# CATS-EUROC-USB.net
KiCad netlist of a schematic drawn in Altium Designer
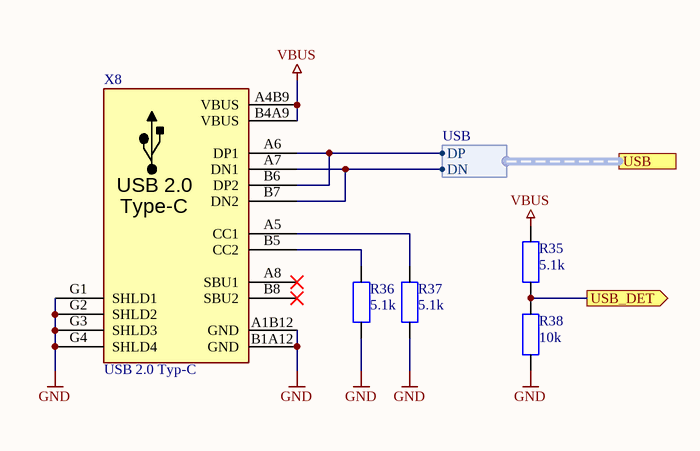
[diagram p0: CATS-EUROC-USB.SchDoc]

(export (version "E")
  (design (tool "Eeschema 10.0.6"))
  (components
    (comp (ref "R35")
      (value "5.1k")
      (footprint "SMD Widerstand 0402")
      (description "SMD Chip Resistor E24")
      (libsource (lib "CATS-EUROC") (part "E24 - 5.1k"))
    )
    (comp (ref "R36")
      (value "5.1k")
      (footprint "SMD Widerstand 0402")
      (description "SMD Chip Resistor E24")
      (libsource (lib "") (part "E24 - 5.1k_1"))
    )
    (comp (ref "R37")
      (value "5.1k")
      (footprint "SMD Widerstand 0402")
      (description "SMD Chip Resistor E24")
      (libsource (lib "") (part "E24 - 5.1k_1"))
    )
    (comp (ref "R38")
      (value "10k")
      (footprint "SMD Widerstand 0402")
      (description "SMD Chip Resistor E24")
      (libsource (lib "CATS-EUROC") (part "E24 - 10k"))
    )
    (comp (ref "X8")
      (value "USB 2.0 Typ-C")
      (footprint "THT USB-C Socket (A40-00119)")
      (description "Typ-C")
      (libsource (lib "CATS-EUROC") (part "USB Type-C USB 2.0"))
    )
  )
  (nets
    (net (code "2") (name "/USB_DET") (class "Default")
      (node (ref "R35") (pin "2") (pinfunction "2_2") (pintype "passive"))
      (node (ref "R38") (pin "1") (pinfunction "1_1") (pintype "passive"))
    )
    (net (code "4") (name "GND") (class "Default")
      (node (ref "R36") (pin "1") (pinfunction "1_1") (pintype "passive"))
      (node (ref "R37") (pin "1") (pinfunction "1_1") (pintype "passive"))
      (node (ref "R38") (pin "2") (pinfunction "2_2") (pintype "passive"))
      (node (ref "X8") (pin "A1B12") (pinfunction "GND_A1B12") (pintype "passive"))
      (node (ref "X8") (pin "B1A12") (pinfunction "GND_B1A12") (pintype "passive"))
      (node (ref "X8") (pin "G1") (pinfunction "SHLD1_G1") (pintype "passive"))
      (node (ref "X8") (pin "G2") (pinfunction "SHLD2_G2") (pintype "passive"))
      (node (ref "X8") (pin "G3") (pinfunction "SHLD3_G3") (pintype "passive"))
      (node (ref "X8") (pin "G4") (pinfunction "SHLD4_G4") (pintype "passive"))
    )
    (net (code "5") (name "Net-(X8-CC1)") (class "Default")
      (node (ref "R37") (pin "2") (pinfunction "2_2") (pintype "passive"))
      (node (ref "X8") (pin "A5") (pinfunction "CC1_A5") (pintype "passive"))
    )
    (net (code "6") (name "Net-(X8-CC2)") (class "Default")
      (node (ref "R36") (pin "2") (pinfunction "2_2") (pintype "passive"))
      (node (ref "X8") (pin "B5") (pinfunction "CC2_B5") (pintype "passive"))
    )
    (net (code "7") (name "Net-(X8-DN1)") (class "Default")
      (node (ref "X8") (pin "A7") (pinfunction "DN1_A7") (pintype "passive"))
      (node (ref "X8") (pin "B7") (pinfunction "DN2_B7") (pintype "passive"))
    )
    (net (code "8") (name "Net-(X8-DP1)") (class "Default")
      (node (ref "X8") (pin "A6") (pinfunction "DP1_A6") (pintype "passive"))
      (node (ref "X8") (pin "B6") (pinfunction "DP2_B6") (pintype "passive"))
    )
    (net (code "9") (name "VBUS") (class "Default")
      (node (ref "R35") (pin "1") (pinfunction "1_1") (pintype "passive"))
      (node (ref "X8") (pin "A4B9") (pinfunction "VBUS_A4B9") (pintype "passive"))
      (node (ref "X8") (pin "B4A9") (pinfunction "VBUS_B4A9") (pintype "passive"))
    )
    (net (code "10") (name "unconnected-(X8-SBU1-PadA8)") (class "Default")
      (node (ref "X8") (pin "A8") (pinfunction "SBU1_A8") (pintype "passive+no_connect"))
    )
    (net (code "11") (name "unconnected-(X8-SBU2-PadB8)") (class "Default")
      (node (ref "X8") (pin "B8") (pinfunction "SBU2_B8") (pintype "passive+no_connect"))
    )
  )
)
